# 2002_A_CapteurMeteoWifi.net
KiCad netlist of a schematic drawn in Altium Designer
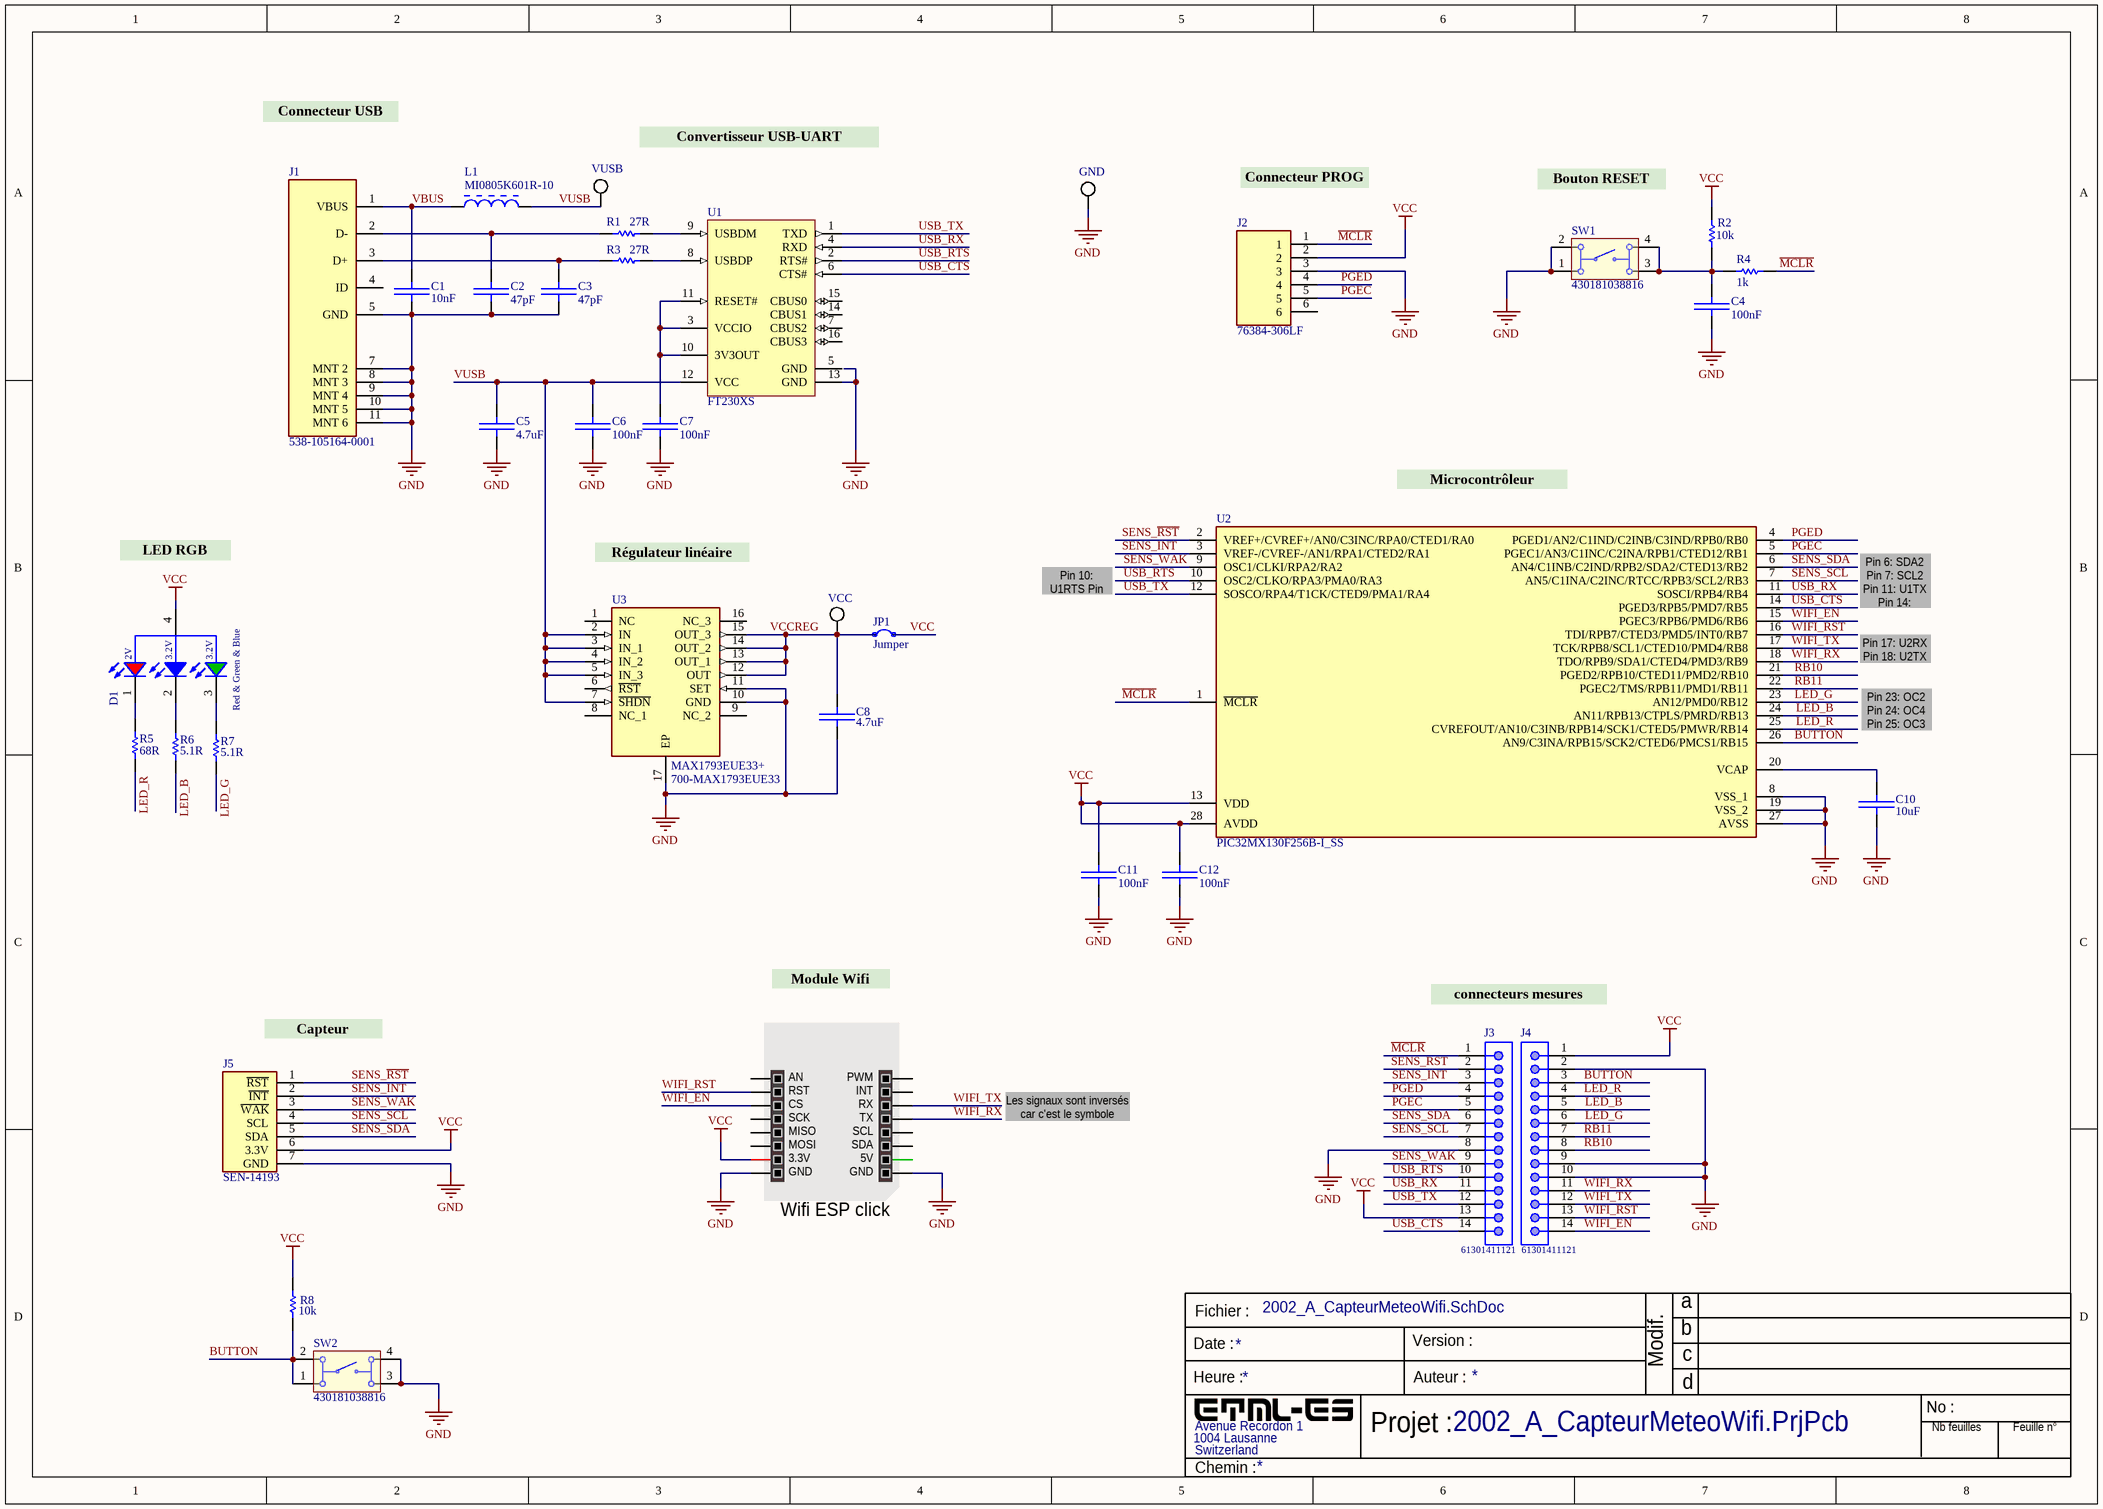
[diagram p0: 2002_A_CapteurMeteoWifi.SchDoc]

(export (version "E")
  (design (tool "Eeschema 10.0.6"))
  (components
    (comp (ref "C1")
      (value "10nF")
      (footprint "LIRD-MI0805K601R-10-2_V")
      (description "0805 Condensator")
      (fields (field (name "Comment") "Condensator"))
      (libsource (lib "2002_CapteurMeteoWifi") (part "Condensator"))
    )
    (comp (ref "C2")
      (value "47pF")
      (footprint "LIRD-MI0805K601R-10-2_V")
      (description "0805 Condensator")
      (fields (field (name "Comment") "Condensator"))
      (libsource (lib "2002_CapteurMeteoWifi") (part "Condensator"))
    )
    (comp (ref "C3")
      (value "47pF")
      (footprint "LIRD-MI0805K601R-10-2_V")
      (description "0805 Condensator")
      (fields (field (name "Comment") "Condensator"))
      (libsource (lib "2002_CapteurMeteoWifi") (part "Condensator"))
    )
    (comp (ref "C4")
      (value "100nF")
      (footprint "LIRD-MI0805K601R-10-2_V")
      (description "0805 Condensator")
      (fields (field (name "Comment") "Condensator"))
      (libsource (lib "2002_CapteurMeteoWifi") (part "Condensator"))
    )
    (comp (ref "C5")
      (value "4.7uF")
      (footprint "LIRD-MI0805K601R-10-2_V")
      (description "0805 Condensator")
      (fields (field (name "Comment") "Condensator"))
      (libsource (lib "2002_CapteurMeteoWifi") (part "Condensator"))
    )
    (comp (ref "C6")
      (value "100nF")
      (footprint "LIRD-MI0805K601R-10-2_V")
      (description "0805 Condensator")
      (fields (field (name "Comment") "Condensator"))
      (libsource (lib "2002_CapteurMeteoWifi") (part "Condensator"))
    )
    (comp (ref "C7")
      (value "100nF")
      (footprint "LIRD-MI0805K601R-10-2_V")
      (description "0805 Condensator")
      (fields (field (name "Comment") "Condensator"))
      (libsource (lib "2002_CapteurMeteoWifi") (part "Condensator"))
    )
    (comp (ref "C8")
      (value "4.7uF")
      (footprint "LIRD-MI0805K601R-10-2_V")
      (description "0805 Condensator")
      (fields (field (name "Comment") "Condensator"))
      (libsource (lib "2002_CapteurMeteoWifi") (part "Condensator"))
    )
    (comp (ref "C10")
      (value "10uF")
      (footprint "LIRD-MI0805K601R-10-2_V")
      (description "0805 Condensator")
      (fields (field (name "Comment") "Condensator"))
      (libsource (lib "2002_CapteurMeteoWifi") (part "Condensator"))
    )
    (comp (ref "C11")
      (value "100nF")
      (footprint "LIRD-MI0805K601R-10-2_V")
      (description "0805 Condensator")
      (fields (field (name "Comment") "Condensator"))
      (libsource (lib "2002_CapteurMeteoWifi") (part "Condensator"))
    )
    (comp (ref "C12")
      (value "100nF")
      (footprint "LIRD-MI0805K601R-10-2_V")
      (description "0805 Condensator")
      (fields (field (name "Comment") "Condensator"))
      (libsource (lib "2002_CapteurMeteoWifi") (part "Condensator"))
    )
    (comp (ref "D1")
      (value "Red & Green & Blue")
      (footprint "150066M153000")
      (description "DEL standard - CMS RGB 0603 SMD")
      (fields (field (name "PART NUMBER") "150066M153000") (field (name "PUBLISHER") "Wurth Elektronik"))
      (libsource (lib "2002_A_CapteurMeteoWifi") (part "APHF1608LSEEQBDZGKC"))
    )
    (comp (ref "GND")
      (value "5019")
      (footprint "TESTPOINT_SMD")
      (description "Test point smd")
      (libsource (lib "2002_CapteurMeteoWifi") (part "TESTPOINT"))
    )
    (comp (ref "J1")
      (value "105164-0001")
      (footprint "Molex_105164-0001_0")
      (description "Connecteurs USB MICRO USB B RECEPT TOP MOUNT")
      (fields (field (name "SUPPLIER PART NUMBER 1") "538-105164-0001"))
      (libsource (lib "2002_CapteurMeteoWifi") (part "105164-0001"))
    )
    (comp (ref "J2")
      (value "76384-306LF")
      (footprint "SHDR6W62P0X254_1X6_1424X460X934P")
      (description "Connector")
      (libsource (lib "2002_CapteurMeteoWifi") (part "76384-306LF"))
    )
    (comp (ref "J3")
      (value "61301411121")
      (footprint "61301411121")
      (description "WR-PHD Pin Header, THT, pitch 2.54mm, Single Row, Vertical, 14pin")
      (fields (field (name "PUBLISHER") "Wurth Elektronik"))
      (libsource (lib "2002_CapteurMeteoWifi") (part "61301411121"))
    )
    (comp (ref "J4")
      (value "61301411121")
      (footprint "61301411121")
      (description "WR-PHD Pin Header, THT, pitch 2.54mm, Single Row, Vertical, 14pin")
      (fields (field (name "PUBLISHER") "Wurth Elektronik"))
      (libsource (lib "2002_CapteurMeteoWifi") (part "61301411121"))
    )
    (comp (ref "J5")
      (value "SEN-14193")
      (footprint "SEN-14193")
      (description "CCS811 kit")
      (fields
        (field (name "MOUSER2 PART NUMBER") "649-68604-804HLF")
        (field (name "MANUFACTURER_PART_NUMBER") "68604-804HLF")
      )
      (libsource (lib "2002_CapteurMeteoWifi") (part "SEN-14193"))
    )
    (comp (ref "JP1")
      (value "Jumper")
      (footprint "connector_2PIN")
      (libsource (lib "2002_CapteurMeteoWifi") (part "Jumper"))
    )
    (comp (ref "L1")
      (value "MI0805K601R-10")
      (footprint "LIRD-MI0805K601R-10-2_V")
      (fields (field (name "MANUFACTURER") "Laird"))
      (libsource (lib "2002_CapteurMeteoWifi") (part "CMP-2000-05196-1"))
    )
    (comp (ref "R1")
      (value "27R")
      (footprint "LIRD-MI0805K601R-10-2_V")
      (description "0805 Resistor")
      (fields (field (name "Comment") "Resistor"))
      (libsource (lib "2002_CapteurMeteoWifi") (part "Resistor"))
    )
    (comp (ref "R2")
      (value "10k")
      (footprint "LIRD-MI0805K601R-10-2_V")
      (description "0805 Resistor")
      (fields (field (name "Comment") "Resistor"))
      (libsource (lib "2002_CapteurMeteoWifi") (part "Resistor"))
    )
    (comp (ref "R3")
      (value "27R")
      (footprint "LIRD-MI0805K601R-10-2_V")
      (description "0805 Resistor")
      (fields (field (name "Comment") "Resistor"))
      (libsource (lib "2002_CapteurMeteoWifi") (part "Resistor"))
    )
    (comp (ref "R4")
      (value "1k")
      (footprint "LIRD-MI0805K601R-10-2_V")
      (description "0805 Resistor")
      (fields (field (name "Comment") "Resistor"))
      (libsource (lib "2002_CapteurMeteoWifi") (part "Resistor"))
    )
    (comp (ref "R5")
      (value "68R")
      (footprint "LIRD-MI0805K601R-10-2_V")
      (description "0805 Resistor")
      (fields (field (name "Comment") "Resistor"))
      (libsource (lib "2002_CapteurMeteoWifi") (part "Resistor"))
    )
    (comp (ref "R6")
      (value "5.1R")
      (footprint "LIRD-MI0805K601R-10-2_V")
      (description "0805 Resistor")
      (fields (field (name "Comment") "Resistor"))
      (libsource (lib "2002_CapteurMeteoWifi") (part "Resistor"))
    )
    (comp (ref "R7")
      (value "5.1R")
      (footprint "LIRD-MI0805K601R-10-2_V")
      (description "0805 Resistor")
      (fields (field (name "Comment") "Resistor"))
      (libsource (lib "2002_CapteurMeteoWifi") (part "Resistor"))
    )
    (comp (ref "R8")
      (value "10k")
      (footprint "LIRD-MI0805K601R-10-2_V")
      (description "0805 Resistor")
      (fields (field (name "Comment") "Resistor"))
      (libsource (lib "2002_CapteurMeteoWifi") (part "Resistor"))
    )
    (comp (ref "SW1")
      (value "430181038816")
      (footprint "430181038816")
      (description "WS-TASV SMD Tact Switch 4.5X4.5 mm")
      (fields (field (name "MANUFACTURER") "Wuerth Elektronik"))
      (libsource (lib "2002_CapteurMeteoWifi") (part "430181038816"))
    )
    (comp (ref "SW2")
      (value "430181038816")
      (footprint "430181038816")
      (description "WS-TASV SMD Tact Switch 4.5X4.5 mm")
      (fields (field (name "MANUFACTURER") "Wuerth Elektronik"))
      (libsource (lib "2002_CapteurMeteoWifi") (part "430181038816"))
    )
    (comp (ref "U1")
      (value "FT230XS")
      (footprint "FTDI-SSOP-16_L")
      (description "USB to Basic UART IC, 2.97 to 5.5 V, -40 to 85 degC, 16-Pin SSOP, RoHS")
      (fields (field (name "MANUFACTURER") "FTDI"))
      (libsource (lib "2002_CapteurMeteoWifi") (part "CMP-2000-06288-1"))
    )
    (comp (ref "U2")
      (value "PIC32MX130F256B-I_SS")
      (footprint "SOP65P780X200-28N")
      (description "Integrated Circuit")
      (fields
        (field (name "MANUFACTURER_PART_NUMBER") "PIC32MX130F256B-I/SS")
        (field (name "MOUSER PART NUMBER") "579-MX130F256BISS")
      )
      (libsource (lib "2002_CapteurMeteoWifi") (part "PIC32MX130F256B-I_SS"))
    )
    (comp (ref "U3")
      (value "MAX1793EUE33+")
      (footprint "SOP65P638X110-17N")
      (description "Integrated Circuit")
      (fields (field (name "SUPPLIER PART NUMBER 1") "700-MAX1793EUE33"))
      (libsource (lib "2002_CapteurMeteoWifi") (part "MAX1793EUE33+"))
    )
    (comp (ref "VCC")
      (value "5019")
      (footprint "TESTPOINT_SMD")
      (description "Test point smd")
      (libsource (lib "2002_CapteurMeteoWifi") (part "TESTPOINT"))
    )
    (comp (ref "VUSB")
      (value "5019")
      (footprint "TESTPOINT_SMD")
      (description "Test point smd")
      (libsource (lib "2002_CapteurMeteoWifi") (part "TESTPOINT"))
    )
    (comp (ref "Wifi ESP click")
      (value "MIKROBUS HOST CONN.")
      (footprint "MIKROBUS HOST CONN.")
      (description "mikroBUS Host Socket")
      (libsource (lib "2002_CapteurMeteoWifi") (part "MIKROBUS HOST CONN._1"))
    )
  )
  (nets
    (net (code "1") (name "/BUTTON") (class "Default")
      (node (ref "J4") (pin "3") (pinfunction "3_3") (pintype "passive"))
      (node (ref "R8") (pin "1") (pinfunction "1_1") (pintype "passive"))
      (node (ref "SW2") (pin "1") (pinfunction "1_1") (pintype "passive"))
      (node (ref "SW2") (pin "2") (pinfunction "2_2") (pintype "passive"))
      (node (ref "U2") (pin "26") (pinfunction "AN9/C3INA/RPB15/SCK2/CTED6/PMCS1/RB15_26") (pintype "passive"))
    )
    (net (code "2") (name "/LED_B") (class "Default")
      (node (ref "J4") (pin "5") (pinfunction "5_5") (pintype "passive"))
      (node (ref "R6") (pin "1") (pinfunction "1_1") (pintype "passive"))
      (node (ref "U2") (pin "24") (pinfunction "AN11/RPB13/CTPLS/PMRD/RB13_24") (pintype "passive"))
    )
    (net (code "3") (name "/LED_G") (class "Default")
      (node (ref "J4") (pin "6") (pinfunction "6_6") (pintype "passive"))
      (node (ref "R7") (pin "1") (pinfunction "1_1") (pintype "passive"))
      (node (ref "U2") (pin "23") (pinfunction "AN12/PMD0/RB12_23") (pintype "passive"))
    )
    (net (code "4") (name "/LED_R") (class "Default")
      (node (ref "J4") (pin "4") (pinfunction "4_4") (pintype "passive"))
      (node (ref "R5") (pin "1") (pinfunction "1_1") (pintype "passive"))
      (node (ref "U2") (pin "25") (pinfunction "CVREFOUT/AN10/C3INB/RPB14/SCK1/CTED5/PMWR/RB14_25") (pintype "passive"))
    )
    (net (code "5") (name "/PGEC") (class "Default")
      (node (ref "J2") (pin "5") (pinfunction "5_5") (pintype "passive"))
      (node (ref "J3") (pin "5") (pinfunction "5_5") (pintype "passive"))
      (node (ref "U2") (pin "5") (pinfunction "PGEC1/AN3/C1INC/C2INA/RPB1/CTED12/RB1_5") (pintype "passive"))
    )
    (net (code "6") (name "/PGED") (class "Default")
      (node (ref "J2") (pin "4") (pinfunction "4_4") (pintype "passive"))
      (node (ref "J3") (pin "4") (pinfunction "4_4") (pintype "passive"))
      (node (ref "U2") (pin "4") (pinfunction "PGED1/AN2/C1IND/C2INB/C3IND/RPB0/RB0_4") (pintype "passive"))
    )
    (net (code "7") (name "/RB10") (class "Default")
      (node (ref "J4") (pin "8") (pinfunction "8_8") (pintype "passive"))
      (node (ref "U2") (pin "21") (pinfunction "PGED2/RPB10/CTED11/PMD2/RB10_21") (pintype "passive"))
    )
    (net (code "8") (name "/RB11") (class "Default")
      (node (ref "J4") (pin "7") (pinfunction "7_7") (pintype "passive"))
      (node (ref "U2") (pin "22") (pinfunction "PGEC2/TMS/RPB11/PMD1/RB11_22") (pintype "passive"))
    )
    (net (code "9") (name "/SENS_SCL") (class "Default")
      (node (ref "J3") (pin "7") (pinfunction "7_7") (pintype "passive"))
      (node (ref "J5") (pin "4") (pinfunction "SCL_4") (pintype "passive"))
      (node (ref "U2") (pin "7") (pinfunction "AN5/C1INA/C2INC/RTCC/RPB3/SCL2/RB3_7") (pintype "passive"))
    )
    (net (code "10") (name "/SENS_SDA") (class "Default")
      (node (ref "J3") (pin "6") (pinfunction "6_6") (pintype "passive"))
      (node (ref "J5") (pin "5") (pinfunction "SDA_5") (pintype "passive"))
      (node (ref "U2") (pin "6") (pinfunction "AN4/C1INB/C2IND/RPB2/SDA2/CTED13/RB2_6") (pintype "passive"))
    )
    (net (code "11") (name "/SENS_~{INT}") (class "Default")
      (node (ref "J3") (pin "3") (pinfunction "3_3") (pintype "passive"))
      (node (ref "J5") (pin "2") (pinfunction "~{INT}_2") (pintype "passive"))
      (node (ref "U2") (pin "3") (pinfunction "VREF-/CVREF-/AN1/RPA1/CTED2/RA1_3") (pintype "passive"))
    )
    (net (code "12") (name "/SENS_~{RST}") (class "Default")
      (node (ref "J3") (pin "2") (pinfunction "2_2") (pintype "passive"))
      (node (ref "J5") (pin "1") (pinfunction "~{RST}_1") (pintype "passive"))
      (node (ref "U2") (pin "2") (pinfunction "VREF+/CVREF+/AN0/C3INC/RPA0/CTED1/RA0_2") (pintype "passive"))
    )
    (net (code "13") (name "/SENS_~{WAK}") (class "Default")
      (node (ref "J3") (pin "9") (pinfunction "9_9") (pintype "passive"))
      (node (ref "J5") (pin "3") (pinfunction "~{WAK}_3") (pintype "passive"))
      (node (ref "U2") (pin "9") (pinfunction "OSC1/CLKI/RPA2/RA2_9") (pintype "passive"))
    )
    (net (code "14") (name "/USB_CTS") (class "Default")
      (node (ref "J3") (pin "14") (pinfunction "14_14") (pintype "passive"))
      (node (ref "U1") (pin "6") (pinfunction "CTS#_6") (pintype "input"))
      (node (ref "U2") (pin "14") (pinfunction "PGED3/RPB5/PMD7/RB5_14") (pintype "passive"))
    )
    (net (code "15") (name "/USB_RTS") (class "Default")
      (node (ref "J3") (pin "10") (pinfunction "10_10") (pintype "passive"))
      (node (ref "U1") (pin "2") (pinfunction "RTS#_2") (pintype "output"))
      (node (ref "U2") (pin "10") (pinfunction "OSC2/CLKO/RPA3/PMA0/RA3_10") (pintype "passive"))
    )
    (net (code "16") (name "/USB_RX") (class "Default")
      (node (ref "J3") (pin "11") (pinfunction "11_11") (pintype "passive"))
      (node (ref "U1") (pin "4") (pinfunction "RXD_4") (pintype "input"))
      (node (ref "U2") (pin "11") (pinfunction "SOSCI/RPB4/RB4_11") (pintype "passive"))
    )
    (net (code "17") (name "/USB_TX") (class "Default")
      (node (ref "J3") (pin "12") (pinfunction "12_12") (pintype "passive"))
      (node (ref "U1") (pin "1") (pinfunction "TXD_1") (pintype "output"))
      (node (ref "U2") (pin "12") (pinfunction "SOSCO/RPA4/T1CK/CTED9/PMA1/RA4_12") (pintype "passive"))
    )
    (net (code "18") (name "/VBUS") (class "Default")
      (node (ref "C1") (pin "1") (pinfunction "1_1") (pintype "passive"))
      (node (ref "J1") (pin "1") (pinfunction "VBUS_1") (pintype "passive"))
      (node (ref "L1") (pin "1") (pinfunction "1_1") (pintype "passive"))
    )
    (net (code "19") (name "/VCCREG") (class "Default")
      (node (ref "C8") (pin "1") (pinfunction "1_1") (pintype "passive"))
      (node (ref "JP1") (pin "1") (pinfunction "1_1") (pintype "passive"))
      (node (ref "U3") (pin "12") (pinfunction "OUT_12") (pintype "output"))
      (node (ref "U3") (pin "13") (pinfunction "OUT_1_13") (pintype "output"))
      (node (ref "U3") (pin "14") (pinfunction "OUT_2_14") (pintype "output"))
      (node (ref "U3") (pin "15") (pinfunction "OUT_3_15") (pintype "output"))
      (node (ref "VCC") (pin "1") (pinfunction "1_1") (pintype "passive"))
    )
    (net (code "20") (name "/VUSB") (class "Default")
      (node (ref "C5") (pin "1") (pinfunction "1_1") (pintype "passive"))
      (node (ref "C6") (pin "1") (pinfunction "1_1") (pintype "passive"))
      (node (ref "L1") (pin "2") (pinfunction "2_2") (pintype "passive"))
      (node (ref "U1") (pin "12") (pinfunction "VCC_12") (pintype "power_in"))
      (node (ref "U3") (pin "2") (pinfunction "IN_2") (pintype "input"))
      (node (ref "U3") (pin "3") (pinfunction "IN_1_3") (pintype "input"))
      (node (ref "U3") (pin "4") (pinfunction "IN_2_4") (pintype "input"))
      (node (ref "U3") (pin "5") (pinfunction "IN_3_5") (pintype "input"))
      (node (ref "U3") (pin "7") (pinfunction "~{SHDN}_7") (pintype "input"))
      (node (ref "VUSB") (pin "1") (pinfunction "1_1") (pintype "passive"))
    )
    (net (code "21") (name "/WIFI_EN") (class "Default")
      (node (ref "J4") (pin "14") (pinfunction "14_14") (pintype "passive"))
      (node (ref "U2") (pin "15") (pinfunction "PGEC3/RPB6/PMD6/RB6_15") (pintype "passive"))
      (node (ref "Wifi ESP click") (pin "3") (pinfunction "CS_3") (pintype "passive"))
    )
    (net (code "22") (name "/WIFI_RST") (class "Default")
      (node (ref "J4") (pin "13") (pinfunction "13_13") (pintype "passive"))
      (node (ref "U2") (pin "16") (pinfunction "TDI/RPB7/CTED3/PMD5/INT0/RB7_16") (pintype "passive"))
      (node (ref "Wifi ESP click") (pin "2") (pinfunction "RST_2") (pintype "passive"))
    )
    (net (code "23") (name "/WIFI_RX") (class "Default")
      (node (ref "J4") (pin "11") (pinfunction "11_11") (pintype "passive"))
      (node (ref "U2") (pin "18") (pinfunction "TDO/RPB9/SDA1/CTED4/PMD3/RB9_18") (pintype "passive"))
      (node (ref "Wifi ESP click") (pin "13") (pinfunction "TX_13") (pintype "passive"))
    )
    (net (code "24") (name "/WIFI_TX") (class "Default")
      (node (ref "J4") (pin "12") (pinfunction "12_12") (pintype "passive"))
      (node (ref "U2") (pin "17") (pinfunction "TCK/RPB8/SCL1/CTED10/PMD4/RB8_17") (pintype "passive"))
      (node (ref "Wifi ESP click") (pin "14") (pinfunction "RX_14") (pintype "passive"))
    )
    (net (code "25") (name "/~{MCLR}") (class "Default")
      (node (ref "J2") (pin "1") (pinfunction "1_1") (pintype "passive"))
      (node (ref "J3") (pin "1") (pinfunction "1_1") (pintype "passive"))
      (node (ref "R4") (pin "1") (pinfunction "1_1") (pintype "passive"))
      (node (ref "U2") (pin "1") (pinfunction "~{MCLR}_1") (pintype "passive"))
    )
    (net (code "26") (name "GND") (class "Default")
      (node (ref "C1") (pin "2") (pinfunction "2_2") (pintype "passive"))
      (node (ref "C10") (pin "2") (pinfunction "2_2") (pintype "passive"))
      (node (ref "C11") (pin "2") (pinfunction "2_2") (pintype "passive"))
      (node (ref "C12") (pin "2") (pinfunction "2_2") (pintype "passive"))
      (node (ref "C2") (pin "2") (pinfunction "2_2") (pintype "passive"))
      (node (ref "C3") (pin "2") (pinfunction "2_2") (pintype "passive"))
      (node (ref "C4") (pin "2") (pinfunction "2_2") (pintype "passive"))
      (node (ref "C5") (pin "2") (pinfunction "2_2") (pintype "passive"))
      (node (ref "C6") (pin "2") (pinfunction "2_2") (pintype "passive"))
      (node (ref "C7") (pin "2") (pinfunction "2_2") (pintype "passive"))
      (node (ref "C8") (pin "2") (pinfunction "2_2") (pintype "passive"))
      (node (ref "GND") (pin "1") (pinfunction "1_1") (pintype "passive"))
      (node (ref "J1") (pin "10") (pinfunction "MNT_5_10") (pintype "passive"))
      (node (ref "J1") (pin "11") (pinfunction "MNT_6_11") (pintype "passive"))
      (node (ref "J1") (pin "5") (pinfunction "GND_5") (pintype "passive"))
      (node (ref "J1") (pin "7") (pinfunction "MNT_2_7") (pintype "passive"))
      (node (ref "J1") (pin "8") (pinfunction "MNT_3_8") (pintype "passive"))
      (node (ref "J1") (pin "9") (pinfunction "MNT_4_9") (pintype "passive"))
      (node (ref "J2") (pin "3") (pinfunction "3_3") (pintype "passive"))
      (node (ref "J3") (pin "8") (pinfunction "8_8") (pintype "passive"))
      (node (ref "J4") (pin "10") (pinfunction "10_10") (pintype "passive"))
      (node (ref "J4") (pin "2") (pinfunction "2_2") (pintype "passive"))
      (node (ref "J4") (pin "9") (pinfunction "9_9") (pintype "passive"))
      (node (ref "J5") (pin "7") (pinfunction "GND_7") (pintype "passive"))
      (node (ref "SW1") (pin "1") (pinfunction "1_1") (pintype "passive"))
      (node (ref "SW1") (pin "2") (pinfunction "2_2") (pintype "passive"))
      (node (ref "SW2") (pin "3") (pinfunction "3_3") (pintype "passive"))
      (node (ref "SW2") (pin "4") (pinfunction "4_4") (pintype "passive"))
      (node (ref "U1") (pin "13") (pinfunction "GND_13") (pintype "power_in"))
      (node (ref "U2") (pin "19") (pinfunction "VSS_2_19") (pintype "passive"))
      (node (ref "U2") (pin "27") (pinfunction "AVSS_27") (pintype "passive"))
      (node (ref "U2") (pin "8") (pinfunction "VSS_1_8") (pintype "passive"))
      (node (ref "U3") (pin "10") (pinfunction "GND_10") (pintype "power_in"))
      (node (ref "U3") (pin "11") (pinfunction "SET_11") (pintype "input"))
      (node (ref "U3") (pin "17") (pinfunction "EP_17") (pintype "passive"))
      (node (ref "Wifi ESP click") (pin "8") (pinfunction "GND_8") (pintype "passive"))
      (node (ref "Wifi ESP click") (pin "9") (pinfunction "GND_9") (pintype "passive"))
    )
    (net (code "27") (name "Net-(C4-Pad1)") (class "Default")
      (node (ref "C4") (pin "1") (pinfunction "1_1") (pintype "passive"))
      (node (ref "R2") (pin "1") (pinfunction "1_1") (pintype "passive"))
      (node (ref "R4") (pin "2") (pinfunction "2_2") (pintype "passive"))
      (node (ref "SW1") (pin "3") (pinfunction "3_3") (pintype "passive"))
      (node (ref "SW1") (pin "4") (pinfunction "4_4") (pintype "passive"))
    )
    (net (code "28") (name "Net-(D1-K-Pad1)") (class "Default")
      (node (ref "D1") (pin "1") (pinfunction "K_1") (pintype "passive"))
      (node (ref "R5") (pin "2") (pinfunction "2_2") (pintype "passive"))
    )
    (net (code "29") (name "Net-(D1-K-Pad2)") (class "Default")
      (node (ref "D1") (pin "2") (pinfunction "K_2") (pintype "passive"))
      (node (ref "R6") (pin "2") (pinfunction "2_2") (pintype "passive"))
    )
    (net (code "30") (name "Net-(D1-K-Pad3)") (class "Default")
      (node (ref "D1") (pin "3") (pinfunction "K_3") (pintype "passive"))
      (node (ref "R7") (pin "2") (pinfunction "2_2") (pintype "passive"))
    )
    (net (code "31") (name "Net-(J1-D+)") (class "Default")
      (node (ref "C3") (pin "1") (pinfunction "1_1") (pintype "passive"))
      (node (ref "J1") (pin "3") (pinfunction "D+_3") (pintype "passive"))
      (node (ref "R3") (pin "1") (pinfunction "1_1") (pintype "passive"))
    )
    (net (code "32") (name "Net-(J1-D-)") (class "Default")
      (node (ref "C2") (pin "1") (pinfunction "1_1") (pintype "passive"))
      (node (ref "J1") (pin "2") (pinfunction "D-_2") (pintype "passive"))
      (node (ref "R1") (pin "1") (pinfunction "1_1") (pintype "passive"))
    )
    (net (code "33") (name "Net-(U1-3V3OUT)") (class "Default")
      (node (ref "C7") (pin "1") (pinfunction "1_1") (pintype "passive"))
      (node (ref "U1") (pin "10") (pinfunction "3V3OUT_10") (pintype "power_in"))
      (node (ref "U1") (pin "11") (pinfunction "RESET#_11") (pintype "input"))
      (node (ref "U1") (pin "3") (pinfunction "VCCIO_3") (pintype "power_in"))
    )
    (net (code "34") (name "Net-(U1-USBDM)") (class "Default")
      (node (ref "R1") (pin "2") (pinfunction "2_2") (pintype "passive"))
      (node (ref "U1") (pin "9") (pinfunction "USBDM_9") (pintype "input"))
    )
    (net (code "35") (name "Net-(U1-USBDP)") (class "Default")
      (node (ref "R3") (pin "2") (pinfunction "2_2") (pintype "passive"))
      (node (ref "U1") (pin "8") (pinfunction "USBDP_8") (pintype "input"))
    )
    (net (code "36") (name "Net-(U2-VCAP)") (class "Default")
      (node (ref "C10") (pin "1") (pinfunction "1_1") (pintype "passive"))
      (node (ref "U2") (pin "20") (pinfunction "VCAP_20") (pintype "passive"))
    )
    (net (code "37") (name "VCC") (class "Default")
      (node (ref "C11") (pin "1") (pinfunction "1_1") (pintype "passive"))
      (node (ref "C12") (pin "1") (pinfunction "1_1") (pintype "passive"))
      (node (ref "D1") (pin "4") (pinfunction "A_4") (pintype "passive"))
      (node (ref "J2") (pin "2") (pinfunction "2_2") (pintype "passive"))
      (node (ref "J3") (pin "13") (pinfunction "13_13") (pintype "passive"))
      (node (ref "J4") (pin "1") (pinfunction "1_1") (pintype "passive"))
      (node (ref "J5") (pin "6") (pinfunction "3.3V_6") (pintype "passive"))
      (node (ref "JP1") (pin "2") (pinfunction "2_2") (pintype "passive"))
      (node (ref "R2") (pin "2") (pinfunction "2_2") (pintype "passive"))
      (node (ref "R8") (pin "2") (pinfunction "2_2") (pintype "passive"))
      (node (ref "U2") (pin "13") (pinfunction "VDD_13") (pintype "passive"))
      (node (ref "U2") (pin "28") (pinfunction "AVDD_28") (pintype "passive"))
      (node (ref "Wifi ESP click") (pin "7") (pinfunction "3.3V_7") (pintype "passive"))
    )
    (net (code "38") (name "unconnected-(J1-ID-Pad4)") (class "Default")
      (node (ref "J1") (pin "4") (pinfunction "ID_4") (pintype "passive"))
    )
    (net (code "39") (name "unconnected-(J2-Pad6)") (class "Default")
      (node (ref "J2") (pin "6") (pinfunction "6_6") (pintype "passive"))
    )
    (net (code "40") (name "unconnected-(U1-CBUS0-Pad15)") (class "Default")
      (node (ref "U1") (pin "15") (pinfunction "CBUS0_15") (pintype "bidirectional"))
    )
    (net (code "41") (name "unconnected-(U1-CBUS1-Pad14)") (class "Default")
      (node (ref "U1") (pin "14") (pinfunction "CBUS1_14") (pintype "bidirectional"))
    )
    (net (code "42") (name "unconnected-(U1-CBUS2-Pad7)") (class "Default")
      (node (ref "U1") (pin "7") (pinfunction "CBUS2_7") (pintype "bidirectional"))
    )
    (net (code "43") (name "unconnected-(U1-CBUS3-Pad16)") (class "Default")
      (node (ref "U1") (pin "16") (pinfunction "CBUS3_16") (pintype "bidirectional"))
    )
    (net (code "44") (name "unconnected-(U1-GND-Pad5)") (class "Default")
      (node (ref "U1") (pin "5") (pinfunction "GND_5") (pintype "power_in"))
    )
    (net (code "45") (name "unconnected-(U3-NC-Pad1)") (class "Default")
      (node (ref "U3") (pin "1") (pinfunction "NC_1") (pintype "passive"))
    )
    (net (code "46") (name "unconnected-(U3-NC_1-Pad8)") (class "Default")
      (node (ref "U3") (pin "8") (pinfunction "NC_1_8") (pintype "passive"))
    )
    (net (code "47") (name "unconnected-(U3-NC_2-Pad9)") (class "Default")
      (node (ref "U3") (pin "9") (pinfunction "NC_2_9") (pintype "passive"))
    )
    (net (code "48") (name "unconnected-(U3-NC_3-Pad16)") (class "Default")
      (node (ref "U3") (pin "16") (pinfunction "NC_3_16") (pintype "passive"))
    )
    (net (code "49") (name "unconnected-(U3-~{RST}-Pad6)") (class "Default")
      (node (ref "U3") (pin "6") (pinfunction "~{RST}_6") (pintype "output"))
    )
    (net (code "50") (name "unconnected-(Wifi ESP click-5V-Pad10)") (class "Default")
      (node (ref "Wifi ESP click") (pin "10") (pinfunction "5V_10") (pintype "passive"))
    )
    (net (code "51") (name "unconnected-(Wifi ESP click-AN-Pad1)") (class "Default")
      (node (ref "Wifi ESP click") (pin "1") (pinfunction "AN_1") (pintype "passive"))
    )
    (net (code "52") (name "unconnected-(Wifi ESP click-INT-Pad15)") (class "Default")
      (node (ref "Wifi ESP click") (pin "15") (pinfunction "INT_15") (pintype "passive"))
    )
    (net (code "53") (name "unconnected-(Wifi ESP click-MISO-Pad5)") (class "Default")
      (node (ref "Wifi ESP click") (pin "5") (pinfunction "MISO_5") (pintype "passive"))
    )
    (net (code "54") (name "unconnected-(Wifi ESP click-MOSI-Pad6)") (class "Default")
      (node (ref "Wifi ESP click") (pin "6") (pinfunction "MOSI_6") (pintype "passive"))
    )
    (net (code "55") (name "unconnected-(Wifi ESP click-PWM-Pad16)") (class "Default")
      (node (ref "Wifi ESP click") (pin "16") (pinfunction "PWM_16") (pintype "passive"))
    )
    (net (code "56") (name "unconnected-(Wifi ESP click-SCK-Pad4)") (class "Default")
      (node (ref "Wifi ESP click") (pin "4") (pinfunction "SCK_4") (pintype "passive"))
    )
    (net (code "57") (name "unconnected-(Wifi ESP click-SCL-Pad12)") (class "Default")
      (node (ref "Wifi ESP click") (pin "12") (pinfunction "SCL_12") (pintype "passive"))
    )
    (net (code "58") (name "unconnected-(Wifi ESP click-SDA-Pad11)") (class "Default")
      (node (ref "Wifi ESP click") (pin "11") (pinfunction "SDA_11") (pintype "passive"))
    )
  )
)
